# nrf51_hid_joy.net
KiCad netlist of a schematic drawn in EAGLE
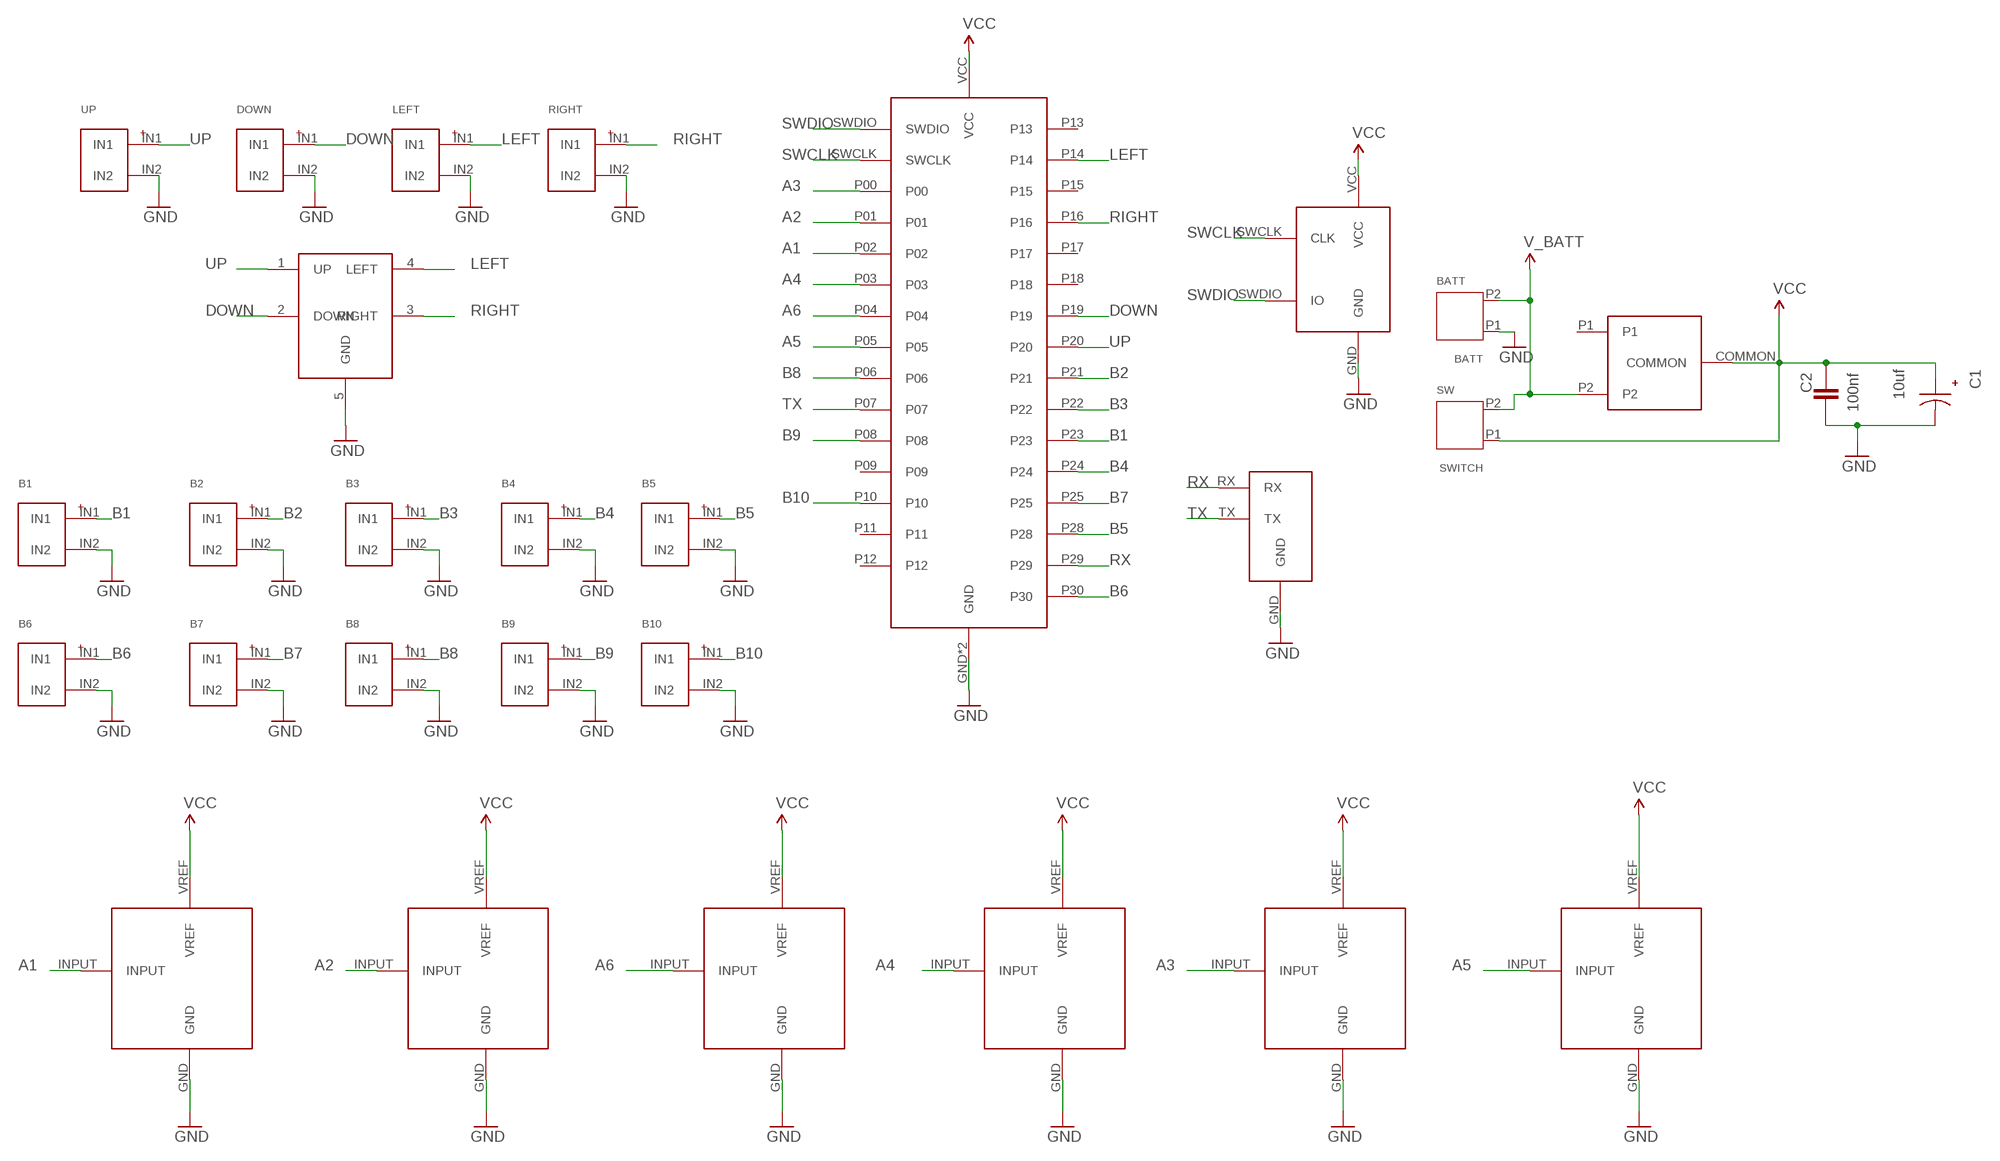
[diagram p0: schematic, sheet 1]

(export (version "E")
  (design (tool "Eeschema 10.0.6"))
  (components
    (comp (ref "A1")
      (value "A1")
      (footprint "eagle-import:ANALOG_INPUT")
      (libsource (lib "eagle-import") (part "ANALOG_INPUT2.54"))
    )
    (comp (ref "A2")
      (value "A2")
      (footprint "eagle-import:ANALOG_INPUT")
      (libsource (lib "eagle-import") (part "ANALOG_INPUT2.54"))
    )
    (comp (ref "A3")
      (value "A3")
      (footprint "eagle-import:ANALOG_INPUT")
      (libsource (lib "eagle-import") (part "ANALOG_INPUT2.54"))
    )
    (comp (ref "A4")
      (value "A4")
      (footprint "eagle-import:ANALOG_INPUT")
      (libsource (lib "eagle-import") (part "ANALOG_INPUT2.54"))
    )
    (comp (ref "A5")
      (value "A5")
      (footprint "eagle-import:ANALOG_INPUT")
      (libsource (lib "eagle-import") (part "ANALOG_INPUT2.54"))
    )
    (comp (ref "A6")
      (value "A6")
      (footprint "eagle-import:ANALOG_INPUT")
      (libsource (lib "eagle-import") (part "ANALOG_INPUT2.54"))
    )
    (comp (ref "B1")
      (value "B1")
      (footprint "eagle-import:JST254")
      (libsource (lib "eagle-import") (part "JST254"))
    )
    (comp (ref "B2")
      (value "B2")
      (footprint "eagle-import:JST254")
      (libsource (lib "eagle-import") (part "JST254"))
    )
    (comp (ref "B3")
      (value "B3")
      (footprint "eagle-import:JST254")
      (libsource (lib "eagle-import") (part "JST254"))
    )
    (comp (ref "B4")
      (value "B4")
      (footprint "eagle-import:JST254")
      (libsource (lib "eagle-import") (part "JST254"))
    )
    (comp (ref "B5")
      (value "B5")
      (footprint "eagle-import:JST254")
      (libsource (lib "eagle-import") (part "JST254"))
    )
    (comp (ref "B6")
      (value "B6")
      (footprint "eagle-import:JST254")
      (libsource (lib "eagle-import") (part "JST254"))
    )
    (comp (ref "B7")
      (value "B7")
      (footprint "eagle-import:JST254")
      (libsource (lib "eagle-import") (part "JST254"))
    )
    (comp (ref "B8")
      (value "B8")
      (footprint "eagle-import:JST254")
      (libsource (lib "eagle-import") (part "JST254"))
    )
    (comp (ref "B9")
      (value "B9")
      (footprint "eagle-import:JST254")
      (libsource (lib "eagle-import") (part "JST254"))
    )
    (comp (ref "B10")
      (value "B10")
      (footprint "eagle-import:JST254")
      (libsource (lib "eagle-import") (part "JST254"))
    )
    (comp (ref "BATT")
      (value "BATT")
      (footprint "eagle-import:2P-3.5")
      (libsource (lib "eagle-import") (part "SCREW-TERM-2P3.5"))
    )
    (comp (ref "C1")
      (value "10uf")
      (footprint "eagle-import:CAPA-RAD-MEDIUM")
      (libsource (lib "eagle-import") (part "CAP_POLPTH1"))
    )
    (comp (ref "C2")
      (value "100nf")
      (footprint "eagle-import:0805")
      (libsource (lib "eagle-import") (part "CAP0805"))
    )
    (comp (ref "DOWN")
      (value "DOWN")
      (footprint "eagle-import:JST254")
      (libsource (lib "eagle-import") (part "JST254"))
    )
    (comp (ref "LEFT")
      (value "LEFT")
      (footprint "eagle-import:JST254")
      (libsource (lib "eagle-import") (part "JST254"))
    )
    (comp (ref "RIGHT")
      (value "RIGHT")
      (footprint "eagle-import:JST254")
      (libsource (lib "eagle-import") (part "JST254"))
    )
    (comp (ref "SWITCH")
      (value "SW")
      (footprint "eagle-import:2P-3.5")
      (libsource (lib "eagle-import") (part "SCREW-TERM-2P3.5"))
    )
    (comp (ref "U$1")
      (value "NRF51_MODULEBIG")
      (footprint "eagle-import:NRF51-MODULE")
      (libsource (lib "eagle-import") (part "NRF51_MODULEBIG"))
    )
    (comp (ref "U$2")
      (value "NRF51_PROG")
      (footprint "eagle-import:PROG_SWD")
      (libsource (lib "eagle-import") (part "NRF51_PROG"))
    )
    (comp (ref "U$3")
      (value "NRF51_SERIAL")
      (footprint "eagle-import:NRF51_SERIAL")
      (libsource (lib "eagle-import") (part "NRF51_SERIAL"))
    )
    (comp (ref "U$14")
      (value "5_5PINS_JOY")
      (footprint "eagle-import:5_PINS_CONNECTOR")
      (libsource (lib "eagle-import") (part "5_5PINS_JOY"))
    )
    (comp (ref "U$23")
      (value "SWITCH")
      (footprint "eagle-import:SS-12D00G3")
      (libsource (lib "eagle-import") (part "SWITCH"))
    )
    (comp (ref "UP")
      (value "UP")
      (footprint "eagle-import:JST254")
      (libsource (lib "eagle-import") (part "JST254"))
    )
  )
  (nets
    (net (code "1") (name "/A1") (class "Default")
      (node (ref "A1") (pin "INPUT") (pinfunction "INPUT_INPUT") (pintype "bidirectional"))
      (node (ref "U$1") (pin "P02") (pinfunction "P02_P02") (pintype "bidirectional"))
    )
    (net (code "2") (name "/A2") (class "Default")
      (node (ref "A2") (pin "INPUT") (pinfunction "INPUT_INPUT") (pintype "bidirectional"))
      (node (ref "U$1") (pin "P01") (pinfunction "P01_P01") (pintype "bidirectional"))
    )
    (net (code "3") (name "/A3") (class "Default")
      (node (ref "A3") (pin "INPUT") (pinfunction "INPUT_INPUT") (pintype "bidirectional"))
      (node (ref "U$1") (pin "P00") (pinfunction "P00_P00") (pintype "bidirectional"))
    )
    (net (code "4") (name "/A4") (class "Default")
      (node (ref "A4") (pin "INPUT") (pinfunction "INPUT_INPUT") (pintype "bidirectional"))
      (node (ref "U$1") (pin "P03") (pinfunction "P03_P03") (pintype "bidirectional"))
    )
    (net (code "5") (name "/A5") (class "Default")
      (node (ref "A5") (pin "INPUT") (pinfunction "INPUT_INPUT") (pintype "bidirectional"))
      (node (ref "U$1") (pin "P05") (pinfunction "P05_P05") (pintype "bidirectional"))
    )
    (net (code "6") (name "/A6") (class "Default")
      (node (ref "A6") (pin "INPUT") (pinfunction "INPUT_INPUT") (pintype "bidirectional"))
      (node (ref "U$1") (pin "P04") (pinfunction "P04_P04") (pintype "bidirectional"))
    )
    (net (code "7") (name "/B1") (class "Default")
      (node (ref "B1") (pin "IN1") (pinfunction "IN1_IN1") (pintype "bidirectional"))
      (node (ref "U$1") (pin "P23") (pinfunction "P23_P23") (pintype "bidirectional"))
    )
    (net (code "8") (name "/B2") (class "Default")
      (node (ref "B2") (pin "IN1") (pinfunction "IN1_IN1") (pintype "bidirectional"))
      (node (ref "U$1") (pin "P21") (pinfunction "P21_P21") (pintype "bidirectional"))
    )
    (net (code "9") (name "/B3") (class "Default")
      (node (ref "B3") (pin "IN1") (pinfunction "IN1_IN1") (pintype "bidirectional"))
      (node (ref "U$1") (pin "P22") (pinfunction "P22_P22") (pintype "bidirectional"))
    )
    (net (code "10") (name "/B4") (class "Default")
      (node (ref "B4") (pin "IN1") (pinfunction "IN1_IN1") (pintype "bidirectional"))
      (node (ref "U$1") (pin "P24") (pinfunction "P24_P24") (pintype "bidirectional"))
    )
    (net (code "11") (name "/B5") (class "Default")
      (node (ref "B5") (pin "IN1") (pinfunction "IN1_IN1") (pintype "bidirectional"))
      (node (ref "U$1") (pin "P28") (pinfunction "P28_P28") (pintype "bidirectional"))
    )
    (net (code "12") (name "/B6") (class "Default")
      (node (ref "B6") (pin "IN1") (pinfunction "IN1_IN1") (pintype "bidirectional"))
      (node (ref "U$1") (pin "P30") (pinfunction "P30_P30") (pintype "bidirectional"))
    )
    (net (code "13") (name "/B7") (class "Default")
      (node (ref "B7") (pin "IN1") (pinfunction "IN1_IN1") (pintype "bidirectional"))
      (node (ref "U$1") (pin "P25") (pinfunction "P25_P25") (pintype "bidirectional"))
    )
    (net (code "14") (name "/B8") (class "Default")
      (node (ref "B8") (pin "IN1") (pinfunction "IN1_IN1") (pintype "bidirectional"))
      (node (ref "U$1") (pin "P06") (pinfunction "P06_P06") (pintype "bidirectional"))
    )
    (net (code "15") (name "/B9") (class "Default")
      (node (ref "B9") (pin "IN1") (pinfunction "IN1_IN1") (pintype "bidirectional"))
      (node (ref "U$1") (pin "P08") (pinfunction "P08_P08") (pintype "bidirectional"))
    )
    (net (code "16") (name "/B10") (class "Default")
      (node (ref "B10") (pin "IN1") (pinfunction "IN1_IN1") (pintype "bidirectional"))
      (node (ref "U$1") (pin "P10") (pinfunction "P10_P10") (pintype "bidirectional"))
    )
    (net (code "17") (name "/DOWN") (class "Default")
      (node (ref "DOWN") (pin "IN1") (pinfunction "IN1_IN1") (pintype "bidirectional"))
      (node (ref "U$1") (pin "P19") (pinfunction "P19_P19") (pintype "bidirectional"))
      (node (ref "U$14") (pin "2") (pinfunction "DOWN_2") (pintype "bidirectional"))
    )
    (net (code "18") (name "/LEFT") (class "Default")
      (node (ref "LEFT") (pin "IN1") (pinfunction "IN1_IN1") (pintype "bidirectional"))
      (node (ref "U$1") (pin "P14") (pinfunction "P14_P14") (pintype "bidirectional"))
      (node (ref "U$14") (pin "4") (pinfunction "LEFT_4") (pintype "bidirectional"))
    )
    (net (code "19") (name "/RIGHT") (class "Default")
      (node (ref "RIGHT") (pin "IN1") (pinfunction "IN1_IN1") (pintype "bidirectional"))
      (node (ref "U$1") (pin "P16") (pinfunction "P16_P16") (pintype "bidirectional"))
      (node (ref "U$14") (pin "3") (pinfunction "RIGHT_3") (pintype "bidirectional"))
    )
    (net (code "20") (name "/RX") (class "Default")
      (node (ref "U$1") (pin "P29") (pinfunction "P29_P29") (pintype "bidirectional"))
      (node (ref "U$3") (pin "RX") (pinfunction "RX_RX") (pintype "bidirectional"))
    )
    (net (code "21") (name "/SWCLK") (class "Default")
      (node (ref "U$1") (pin "SWCLK") (pinfunction "SWCLK_SWCLK") (pintype "bidirectional"))
      (node (ref "U$2") (pin "SWCLK") (pinfunction "CLK_SWCLK") (pintype "bidirectional"))
    )
    (net (code "22") (name "/SWDIO") (class "Default")
      (node (ref "U$1") (pin "SWDIO") (pinfunction "SWDIO_SWDIO") (pintype "bidirectional"))
      (node (ref "U$2") (pin "SWDIO") (pinfunction "IO_SWDIO") (pintype "bidirectional"))
    )
    (net (code "23") (name "/TX") (class "Default")
      (node (ref "U$1") (pin "P07") (pinfunction "P07_P07") (pintype "bidirectional"))
      (node (ref "U$3") (pin "TX") (pinfunction "TX_TX") (pintype "bidirectional"))
    )
    (net (code "24") (name "/UP") (class "Default")
      (node (ref "U$1") (pin "P20") (pinfunction "P20_P20") (pintype "bidirectional"))
      (node (ref "U$14") (pin "1") (pinfunction "UP_1") (pintype "bidirectional"))
      (node (ref "UP") (pin "IN1") (pinfunction "IN1_IN1") (pintype "bidirectional"))
    )
    (net (code "25") (name "GND") (class "Default")
      (node (ref "A1") (pin "GND") (pinfunction "GND_GND") (pintype "bidirectional"))
      (node (ref "A2") (pin "GND") (pinfunction "GND_GND") (pintype "bidirectional"))
      (node (ref "A3") (pin "GND") (pinfunction "GND_GND") (pintype "bidirectional"))
      (node (ref "A4") (pin "GND") (pinfunction "GND_GND") (pintype "bidirectional"))
      (node (ref "A5") (pin "GND") (pinfunction "GND_GND") (pintype "bidirectional"))
      (node (ref "A6") (pin "GND") (pinfunction "GND_GND") (pintype "bidirectional"))
      (node (ref "B1") (pin "IN2") (pinfunction "IN2_IN2") (pintype "bidirectional"))
      (node (ref "B10") (pin "IN2") (pinfunction "IN2_IN2") (pintype "bidirectional"))
      (node (ref "B2") (pin "IN2") (pinfunction "IN2_IN2") (pintype "bidirectional"))
      (node (ref "B3") (pin "IN2") (pinfunction "IN2_IN2") (pintype "bidirectional"))
      (node (ref "B4") (pin "IN2") (pinfunction "IN2_IN2") (pintype "bidirectional"))
      (node (ref "B5") (pin "IN2") (pinfunction "IN2_IN2") (pintype "bidirectional"))
      (node (ref "B6") (pin "IN2") (pinfunction "IN2_IN2") (pintype "bidirectional"))
      (node (ref "B7") (pin "IN2") (pinfunction "IN2_IN2") (pintype "bidirectional"))
      (node (ref "B8") (pin "IN2") (pinfunction "IN2_IN2") (pintype "bidirectional"))
      (node (ref "B9") (pin "IN2") (pinfunction "IN2_IN2") (pintype "bidirectional"))
      (node (ref "BATT") (pin "P1") (pinfunction "1_P1") (pintype "bidirectional"))
      (node (ref "C1") (pin "2") (pinfunction "-_2") (pintype "bidirectional"))
      (node (ref "C2") (pin "1") (pinfunction "1_1") (pintype "passive"))
      (node (ref "DOWN") (pin "IN2") (pinfunction "IN2_IN2") (pintype "bidirectional"))
      (node (ref "LEFT") (pin "IN2") (pinfunction "IN2_IN2") (pintype "bidirectional"))
      (node (ref "RIGHT") (pin "IN2") (pinfunction "IN2_IN2") (pintype "bidirectional"))
      (node (ref "U$1") (pin "GND") (pinfunction "GND_GND") (pintype "bidirectional"))
      (node (ref "U$1") (pin "GND2") (pinfunction "GND_GND2") (pintype "bidirectional"))
      (node (ref "U$14") (pin "5") (pinfunction "GND_5") (pintype "bidirectional"))
      (node (ref "U$2") (pin "GND") (pinfunction "GND_GND") (pintype "bidirectional"))
      (node (ref "U$3") (pin "GND") (pinfunction "GND_GND") (pintype "bidirectional"))
      (node (ref "UP") (pin "IN2") (pinfunction "IN2_IN2") (pintype "bidirectional"))
    )
    (net (code "26") (name "VCC") (class "Default")
      (node (ref "A1") (pin "VREF") (pinfunction "VREF_VREF") (pintype "bidirectional"))
      (node (ref "A2") (pin "VREF") (pinfunction "VREF_VREF") (pintype "bidirectional"))
      (node (ref "A3") (pin "VREF") (pinfunction "VREF_VREF") (pintype "bidirectional"))
      (node (ref "A4") (pin "VREF") (pinfunction "VREF_VREF") (pintype "bidirectional"))
      (node (ref "A5") (pin "VREF") (pinfunction "VREF_VREF") (pintype "bidirectional"))
      (node (ref "A6") (pin "VREF") (pinfunction "VREF_VREF") (pintype "bidirectional"))
      (node (ref "C1") (pin "1") (pinfunction "+_1") (pintype "bidirectional"))
      (node (ref "C2") (pin "2") (pinfunction "2_2") (pintype "passive"))
      (node (ref "SWITCH") (pin "P1") (pinfunction "1_P1") (pintype "bidirectional"))
      (node (ref "U$1") (pin "VCC") (pinfunction "VCC_VCC") (pintype "bidirectional"))
      (node (ref "U$2") (pin "VCC") (pinfunction "VCC_VCC") (pintype "bidirectional"))
      (node (ref "U$23") (pin "COMMON") (pinfunction "COMMON_COMMON") (pintype "bidirectional"))
    )
    (net (code "27") (name "V_BATT") (class "Default")
      (node (ref "BATT") (pin "P2") (pinfunction "2_P2") (pintype "bidirectional"))
      (node (ref "SWITCH") (pin "P2") (pinfunction "2_P2") (pintype "bidirectional"))
      (node (ref "U$23") (pin "P2") (pinfunction "P2_P2") (pintype "bidirectional"))
    )
    (net (code "28") (name "unconnected-(U$1-PadP09)") (class "Default")
      (node (ref "U$1") (pin "P09") (pinfunction "P09_P09") (pintype "bidirectional"))
    )
    (net (code "29") (name "unconnected-(U$1-PadP11)") (class "Default")
      (node (ref "U$1") (pin "P11") (pinfunction "P11_P11") (pintype "bidirectional"))
    )
    (net (code "30") (name "unconnected-(U$1-PadP12)") (class "Default")
      (node (ref "U$1") (pin "P12") (pinfunction "P12_P12") (pintype "bidirectional"))
    )
    (net (code "31") (name "unconnected-(U$1-PadP13)") (class "Default")
      (node (ref "U$1") (pin "P13") (pinfunction "P13_P13") (pintype "bidirectional"))
    )
    (net (code "32") (name "unconnected-(U$1-PadP15)") (class "Default")
      (node (ref "U$1") (pin "P15") (pinfunction "P15_P15") (pintype "bidirectional"))
    )
    (net (code "33") (name "unconnected-(U$1-PadP17)") (class "Default")
      (node (ref "U$1") (pin "P17") (pinfunction "P17_P17") (pintype "bidirectional"))
    )
    (net (code "34") (name "unconnected-(U$1-PadP18)") (class "Default")
      (node (ref "U$1") (pin "P18") (pinfunction "P18_P18") (pintype "bidirectional"))
    )
    (net (code "35") (name "unconnected-(U$23-PadP1)") (class "Default")
      (node (ref "U$23") (pin "P1") (pinfunction "P1_P1") (pintype "bidirectional"))
    )
  )
)
